# gsm.net
KiCad netlist of a schematic drawn in Altium Designer
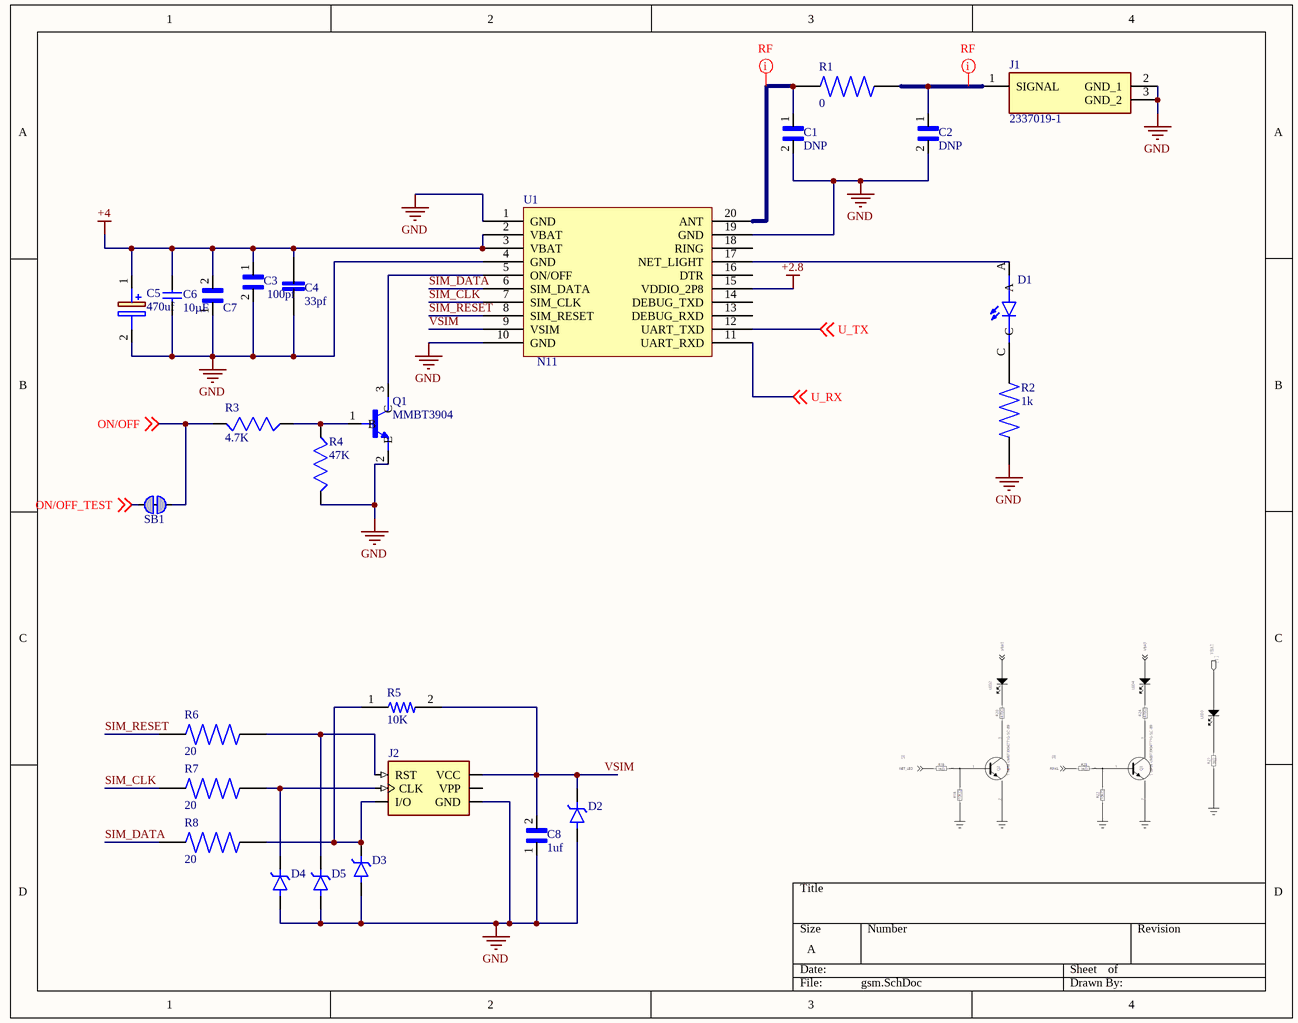
[diagram p0: gsm.SchDoc]

(export (version "E")
  (design (tool "Eeschema 10.0.6"))
  (components
    (comp (ref "C1")
      (value "DNP")
      (footprint "CAPC1608X90")
      (description "CAP, MLCC, X5R, 0.47UF, 10V, 0603")
      (fields (field (name "MP") "C0603C474K8PACTU") (field (name "MF") "{'manufacturer': u'KEMET'}"))
      (libsource (lib "SnapEDA_Library") (part "C0603C474K8PACTU"))
    )
    (comp (ref "C2")
      (value "DNP")
      (footprint "CAPC1608X90")
      (description "CAP, MLCC, X5R, 0.47UF, 10V, 0603")
      (fields (field (name "MP") "C0603C474K8PACTU") (field (name "MF") "{'manufacturer': u'KEMET'}"))
      (libsource (lib "SnapEDA_Library") (part "C0603C474K8PACTU"))
    )
    (comp (ref "C3")
      (value "100pf")
      (footprint "CAPC1608X90")
      (description "0603 100 pF 50 V Â±5% Tolerance NP0 SMT Multilayer Ceramic Capacitor")
      (fields (field (name "MP") "CC0603JPNPO9BN101") (field (name "MF") "{'manufacturer': u'Yageo'}"))
      (libsource (lib "SnapEDA_Library") (part "CC0603JPNPO9BN101"))
    )
    (comp (ref "C4")
      (value "33pf")
      (footprint "CAPC1608X90")
      (description "0603 33 pF 50 V Â±5 % Tolerance C0G/NP0 SMT Multilayer Ceramic Capacitor")
      (fields (field (name "MF") "{'manufacturer': u'Yageo'}") (field (name "MP") "CC0603JPNPO9BN330"))
      (libsource (lib "SnapEDA_Library") (part "CC0603JPNPO9BN330"))
    )
    (comp (ref "C5")
      (value "470uf")
      (footprint "mouser_layout_lib:CAPAE830X1050N")
      (description "Capacitor Polarised")
      (fields
        (field (name "MANUFACTURER_PART_NUMBER") "EDH477M6R3A9MAA")
        (field (name "MOUSER PART NUMBER") "80-EDH477M6R3A9MAA")
      )
      (libsource (lib "mouser_sch_lib") (part "EDH477M6R3A9MAA"))
    )
    (comp (ref "C6")
      (value "10µF")
      (footprint "CAP_0603")
      (description "10µF 10V Ceramic Capacitor X5R 0603 (1608 Metric) 0.063\" L x 0.031\" W (1.60mm x 0.80mm)")
      (fields
        (field (name "MANUFACTURER") "Samsung Electronics")
        (field (name "PART NUMBER") "CL10A106KP8NNNC")
      )
      (libsource (lib "apollo2-amaph1kk-kbr-brd") (part "CL10A106KP8NNNC"))
    )
    (comp (ref "C7")
      (value "06033G104ZAT4A")
      (footprint "CAPC1608X90N")
      (description "Cap Ceramic 0.1uF 25V Y5V -20% to 80% SMD 0603 85C T/R")
      (fields (field (name "MF") "{'manufacturer': u'AVX'}"))
      (libsource (lib "chargebot_alpha") (part "06033G104ZAT4A"))
    )
    (comp (ref "C8")
      (value "1uf")
      (footprint "CAPC1608X90N")
      (fields (field (name "MF") "{'manufacturer': u'Taiyo Yuden'}") (field (name "MP") "EMK107B7105MA-T"))
      (libsource (lib "SnapEDA_Library") (part "EMK107B7105MA-T"))
    )
    (comp (ref "D1")
      (value "LTST-C190KRKT")
      (footprint "LEDC1608X35N")
      (description "LED; SMD; 0603; red; 18-180mcd; 1.6x0.8x0.8mm; 130Â°; 1.6Ã·2.4V; 20mA")
      (fields (field (name "MF") "{'manufacturer': u'Lite-On Inc.'}"))
      (libsource (lib "SnapEDA_Library") (part "LTST-C190KRKT"))
    )
    (comp (ref "D2")
      (value "ESD9X5.0ST5G")
      (footprint "SODFL1006X43N")
      (description "ESD9X5.0S: ESD Protection Single Diode In Ultra Small SOD-923 Package")
      (fields (field (name "MF") "{'manufacturer': u'ON Semiconductor'}"))
      (libsource (lib "SnapEDA_Library") (part "ESD9X5.0ST5G"))
    )
    (comp (ref "D3")
      (value "ESD9X5.0ST5G")
      (footprint "SODFL1006X43N")
      (description "ESD9X5.0S: ESD Protection Single Diode In Ultra Small SOD-923 Package")
      (fields (field (name "MF") "{'manufacturer': u'ON Semiconductor'}"))
      (libsource (lib "SnapEDA_Library") (part "ESD9X5.0ST5G"))
    )
    (comp (ref "D4")
      (value "ESD9X5.0ST5G")
      (footprint "SODFL1006X43N")
      (description "ESD9X5.0S: ESD Protection Single Diode In Ultra Small SOD-923 Package")
      (fields (field (name "MF") "{'manufacturer': u'ON Semiconductor'}"))
      (libsource (lib "SnapEDA_Library") (part "ESD9X5.0ST5G"))
    )
    (comp (ref "D5")
      (value "ESD9X5.0ST5G")
      (footprint "SODFL1006X43N")
      (description "ESD9X5.0S: ESD Protection Single Diode In Ultra Small SOD-923 Package")
      (fields (field (name "MF") "{'manufacturer': u'ON Semiconductor'}"))
      (libsource (lib "SnapEDA_Library") (part "ESD9X5.0ST5G"))
    )
    (comp (ref "J1")
      (value "2337019-1")
      (footprint "mouser_layout_lib:23370191")
      (description "Connector")
      (fields (field (name "MOUSER PART NUMBER") "571-2337019-1"))
      (libsource (lib "mouser_sch_lib") (part "2337019-1"))
    )
    (comp (ref "J2")
      (value "SIM8051-6-0-14-01-X-REVD")
      (footprint "GCT_SIM8051-6-0-14-01-X-REVD")
      (description "Nano SIM Card Connector, Push-Pull Type, 6 Pin, SMT, Profile 1.35mm")
      (fields (field (name "MF") "{'manufacturer': u'Global Connector Technology'}"))
      (libsource (lib "SnapEDA_Library") (part "SIM8051-6-0-14-01-X-REVD"))
    )
    (comp (ref "Q1")
      (value "MMBT3904")
      (footprint "SOT95P240X120-3N")
      (description "MMBT3904 Series 40 V CE Breakdown 0.2 A NPN General Purpose Amplifier - SOT-23")
      (fields (field (name "MF") "{'manufacturer': u'ON Semiconductor'}"))
      (libsource (lib "SnapEDA_Library") (part "MMBT3904"))
    )
    (comp (ref "R1")
      (value "0")
      (footprint "RESC1607X60N")
      (description "Thick film general purpose")
      (fields (field (name "MP") "RC0603JR-070RL") (field (name "MF") "{'manufacturer': u'Yageo'}"))
      (libsource (lib "SnapEDA_Library") (part "RC0603JR-070RL"))
    )
    (comp (ref "R2")
      (value "1k")
      (footprint "RESC1608X55N")
      (description "Resistor; Thick Film; Res 1 Kilohms; Pwr-Rtg 0.1 W; Tol 1%; SMT; 0603")
      (fields (field (name "MP") "CR0603-FX-1001ELF") (field (name "MF") "{'manufacturer': u'Bourns'}"))
      (libsource (lib "SnapEDA_Library") (part "CR0603-FX-1001ELF"))
    )
    (comp (ref "R3")
      (value "4.7K")
      (footprint "RESC1608X55")
      (description "RC Series 0603 0.1 W 47 kOhms 1% Â±100 ppm/Â°C SMT Thick Film Chip Resistor")
      (fields (field (name "MP") "RC0603FR-0747KL") (field (name "MF") "{'manufacturer': u'Yageo'}"))
      (libsource (lib "SnapEDA_Library") (part "RC0603FR-0747KL"))
    )
    (comp (ref "R4")
      (value "47K")
      (footprint "RESC1608X55")
      (description "RC Series 0603 0.1 W 47 kOhms 1% Â±100 ppm/Â°C SMT Thick Film Chip Resistor")
      (fields (field (name "MP") "RC0603FR-0747KL") (field (name "MF") "{'manufacturer': u'Yageo'}"))
      (libsource (lib "SnapEDA_Library") (part "RC0603FR-0747KL"))
    )
    (comp (ref "R5")
      (value "10K")
      (footprint "RESC1607X60N")
      (description "YAGEO RC0603FR-0710KL / RESISTOR 10K 1/10W 1% 0603 YAG")
      (fields (field (name "MF") "{'manufacturer': u'Yageo'}") (field (name "MP") "RC0603FR-0710KL"))
      (libsource (lib "SnapEDA_Library") (part "RC0603FR-0710KL"))
    )
    (comp (ref "R6")
      (value "20")
      (footprint "RESC1607X60N")
      (description "RC Series 0603 0.1 W 20 Ohms 1% Â±100 ppm/Â°C SMT Thick Film Chip Resistor")
      (fields (field (name "MF") "{'manufacturer': u'Yageo'}") (field (name "MP") "RC0603FR-0720RL"))
      (libsource (lib "SnapEDA_Library") (part "RC0603FR-0720RL"))
    )
    (comp (ref "R7")
      (value "20")
      (footprint "RESC1607X60N")
      (description "RC Series 0603 0.1 W 20 Ohms 1% Â±100 ppm/Â°C SMT Thick Film Chip Resistor")
      (fields (field (name "MF") "{'manufacturer': u'Yageo'}") (field (name "MP") "RC0603FR-0720RL"))
      (libsource (lib "SnapEDA_Library") (part "RC0603FR-0720RL"))
    )
    (comp (ref "R8")
      (value "20")
      (footprint "RESC1607X60N")
      (description "RC Series 0603 0.1 W 20 Ohms 1% Â±100 ppm/Â°C SMT Thick Film Chip Resistor")
      (fields (field (name "MF") "{'manufacturer': u'Yageo'}") (field (name "MP") "RC0603FR-0720RL"))
      (libsource (lib "SnapEDA_Library") (part "RC0603FR-0720RL"))
    )
    (comp (ref "SB1")
      (value "Solderbridge")
      (footprint "SOLDERBRIDGE_SHORTED")
      (description "Shorted Solderbridge")
      (fields
        (field (name "PART NUMBER") "Solderbridge Shorted")
        (field (name "PUBLISHER") "Nordic Semiconductor")
      )
      (libsource (lib "apollo2-amaph1kk-kbr-brd") (part "SOLDERBRIDGE_SHORTED"))
    )
    (comp (ref "U1")
      (value "This is Neoway N11 Module")
      (footprint "N11_20P")
      (libsource (lib "N11") (part "N11"))
    )
  )
  (nets
    (net (code "1") (name "+2.8") (class "Default")
      (node (ref "U1") (pin "15") (pinfunction "VDDIO_2P8_15") (pintype "passive"))
    )
    (net (code "2") (name "+4") (class "Default")
      (node (ref "C3") (pin "1") (pinfunction "1_1") (pintype "passive"))
      (node (ref "C4") (pin "2") (pinfunction "2_2") (pintype "passive"))
      (node (ref "C5") (pin "1") (pinfunction "+_1") (pintype "passive"))
      (node (ref "C6") (pin "1") (pinfunction "1_1") (pintype "passive"))
      (node (ref "C7") (pin "2") (pinfunction "2_2") (pintype "passive"))
      (node (ref "U1") (pin "2") (pinfunction "VBAT_2") (pintype "passive"))
      (node (ref "U1") (pin "3") (pinfunction "VBAT_3") (pintype "passive"))
    )
    (net (code "3") (name "/SIM_CLK") (class "Default")
      (node (ref "R7") (pin "1") (pinfunction "1_1") (pintype "passive"))
      (node (ref "U1") (pin "7") (pinfunction "SIM_CLK_7") (pintype "passive"))
    )
    (net (code "4") (name "/SIM_DATA") (class "Default")
      (node (ref "R8") (pin "1") (pinfunction "1_1") (pintype "passive"))
      (node (ref "U1") (pin "6") (pinfunction "SIM_DATA_6") (pintype "passive"))
    )
    (net (code "5") (name "/SIM_RESET") (class "Default")
      (node (ref "R6") (pin "1") (pinfunction "1_1") (pintype "passive"))
      (node (ref "U1") (pin "8") (pinfunction "SIM_RESET_8") (pintype "passive"))
    )
    (net (code "6") (name "/VSIM") (class "Default")
      (node (ref "C8") (pin "2") (pinfunction "2_2") (pintype "passive"))
      (node (ref "D2") (pin "C") (pinfunction "K_C") (pintype "passive"))
      (node (ref "J2") (pin "C1") (pinfunction "VCC_C1") (pintype "power_in"))
      (node (ref "R5") (pin "2") (pinfunction "2_2") (pintype "passive"))
      (node (ref "U1") (pin "9") (pinfunction "VSIM_9") (pintype "passive"))
    )
    (net (code "7") (name "GND") (class "Default")
      (node (ref "C1") (pin "2") (pinfunction "2_2") (pintype "passive"))
      (node (ref "C2") (pin "2") (pinfunction "2_2") (pintype "passive"))
      (node (ref "C3") (pin "2") (pinfunction "2_2") (pintype "passive"))
      (node (ref "C4") (pin "1") (pinfunction "1_1") (pintype "passive"))
      (node (ref "C5") (pin "2") (pinfunction "-_2") (pintype "passive"))
      (node (ref "C6") (pin "2") (pinfunction "2_2") (pintype "passive"))
      (node (ref "C7") (pin "1") (pinfunction "1_1") (pintype "passive"))
      (node (ref "C8") (pin "1") (pinfunction "1_1") (pintype "passive"))
      (node (ref "D2") (pin "A") (pinfunction "A_A") (pintype "passive"))
      (node (ref "D3") (pin "A") (pinfunction "A_A") (pintype "passive"))
      (node (ref "D4") (pin "A") (pinfunction "A_A") (pintype "passive"))
      (node (ref "D5") (pin "A") (pinfunction "A_A") (pintype "passive"))
      (node (ref "J1") (pin "2") (pinfunction "GND_1_2") (pintype "passive"))
      (node (ref "J1") (pin "3") (pinfunction "GND_2_3") (pintype "passive"))
      (node (ref "J2") (pin "C5") (pinfunction "GND_C5") (pintype "power_in"))
      (node (ref "Q1") (pin "2") (pinfunction "E_2") (pintype "passive"))
      (node (ref "R2") (pin "1") (pinfunction "1_1") (pintype "passive"))
      (node (ref "R4") (pin "1") (pinfunction "1_1") (pintype "passive"))
      (node (ref "U1") (pin "1") (pinfunction "GND_1") (pintype "passive"))
      (node (ref "U1") (pin "10") (pinfunction "GND_10") (pintype "passive"))
      (node (ref "U1") (pin "19") (pinfunction "GND_19") (pintype "passive"))
      (node (ref "U1") (pin "4") (pinfunction "GND_4") (pintype "passive"))
    )
    (net (code "8") (name "Net-(D1-PadC)") (class "Default")
      (node (ref "D1") (pin "C") (pinfunction "C_C") (pintype "passive"))
      (node (ref "R2") (pin "2") (pinfunction "2_2") (pintype "passive"))
    )
    (net (code "9") (name "Net-(D3-K)") (class "Default")
      (node (ref "D3") (pin "C") (pinfunction "K_C") (pintype "passive"))
      (node (ref "J2") (pin "C7") (pinfunction "I/O_C7") (pintype "bidirectional"))
      (node (ref "R5") (pin "1") (pinfunction "1_1") (pintype "passive"))
      (node (ref "R8") (pin "2") (pinfunction "2_2") (pintype "passive"))
    )
    (net (code "10") (name "Net-(D4-K)") (class "Default")
      (node (ref "D4") (pin "C") (pinfunction "K_C") (pintype "passive"))
      (node (ref "J2") (pin "C3") (pinfunction "CLK_C3") (pintype "input"))
      (node (ref "R7") (pin "2") (pinfunction "2_2") (pintype "passive"))
    )
    (net (code "11") (name "Net-(D5-K)") (class "Default")
      (node (ref "D5") (pin "C") (pinfunction "K_C") (pintype "passive"))
      (node (ref "J2") (pin "C2") (pinfunction "RST_C2") (pintype "input"))
      (node (ref "R6") (pin "2") (pinfunction "2_2") (pintype "passive"))
    )
    (net (code "12") (name "Net-(J1-SIGNAL)") (class "Default")
      (node (ref "C2") (pin "1") (pinfunction "1_1") (pintype "passive"))
      (node (ref "J1") (pin "1") (pinfunction "SIGNAL_1") (pintype "passive"))
      (node (ref "R1") (pin "2") (pinfunction "2_2") (pintype "passive"))
    )
    (net (code "13") (name "Net-(Q1-B)") (class "Default")
      (node (ref "Q1") (pin "1") (pinfunction "B_1") (pintype "passive"))
      (node (ref "R3") (pin "2") (pinfunction "2_2") (pintype "passive"))
      (node (ref "R4") (pin "2") (pinfunction "2_2") (pintype "passive"))
    )
    (net (code "14") (name "Net-(Q1-C)") (class "Default")
      (node (ref "Q1") (pin "3") (pinfunction "C_3") (pintype "passive"))
      (node (ref "U1") (pin "5") (pinfunction "ON/OFF_5") (pintype "passive"))
    )
    (net (code "15") (name "Net-(U1-ANT)") (class "Default")
      (node (ref "C1") (pin "1") (pinfunction "1_1") (pintype "passive"))
      (node (ref "R1") (pin "1") (pinfunction "1_1") (pintype "passive"))
      (node (ref "U1") (pin "20") (pinfunction "ANT_20") (pintype "passive"))
    )
    (net (code "16") (name "Net-(U1-NET_LIGHT)") (class "Default")
      (node (ref "D1") (pin "A") (pinfunction "A_A") (pintype "passive"))
      (node (ref "U1") (pin "17") (pinfunction "NET_LIGHT_17") (pintype "passive"))
    )
    (net (code "17") (name "ON{slash}OFF") (class "Default")
      (node (ref "R3") (pin "1") (pinfunction "1_1") (pintype "passive"))
      (node (ref "SB1") (pin "1") (pinfunction "0_1") (pintype "passive"))
    )
    (net (code "18") (name "ON{slash}OFF_TEST") (class "Default")
      (node (ref "SB1") (pin "2") (pinfunction "1_2") (pintype "passive"))
    )
    (net (code "19") (name "U_RX") (class "Default")
      (node (ref "U1") (pin "11") (pinfunction "UART_RXD_11") (pintype "passive"))
    )
    (net (code "20") (name "U_TX") (class "Default")
      (node (ref "U1") (pin "12") (pinfunction "UART_TXD_12") (pintype "passive"))
    )
    (net (code "21") (name "unconnected-(J2-VPP-PadC6)") (class "Default")
      (node (ref "J2") (pin "C6") (pinfunction "VPP_C6") (pintype "power_in"))
    )
    (net (code "22") (name "unconnected-(U1-DEBUG_RXD-Pad13)") (class "Default")
      (node (ref "U1") (pin "13") (pinfunction "DEBUG_RXD_13") (pintype "passive"))
    )
    (net (code "23") (name "unconnected-(U1-DEBUG_TXD-Pad14)") (class "Default")
      (node (ref "U1") (pin "14") (pinfunction "DEBUG_TXD_14") (pintype "passive"))
    )
    (net (code "24") (name "unconnected-(U1-DTR-Pad16)") (class "Default")
      (node (ref "U1") (pin "16") (pinfunction "DTR_16") (pintype "passive"))
    )
    (net (code "25") (name "unconnected-(U1-RING-Pad18)") (class "Default")
      (node (ref "U1") (pin "18") (pinfunction "RING_18") (pintype "passive"))
    )
  )
)
